# 5V_Regulator.net
KiCad netlist of a schematic drawn in Altium Designer
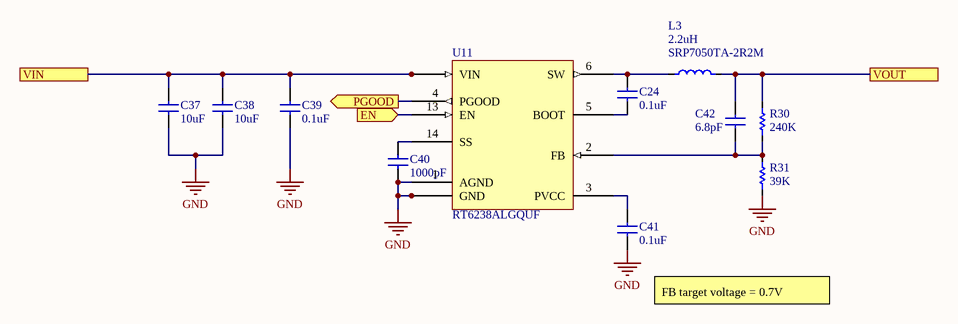
[diagram p0: 5V_Regulator.SchDoc]

(export (version "E")
  (design (tool "Eeschema 10.0.6"))
  (components
    (comp (ref "C24")
      (value "0.1uF")
      (footprint "0603_CAPACITOR")
      (description "CAP CERM 0.1uF 10% 50V 0603")
      (fields
        (field (name "VOLTAGE") "50V")
        (field (name "Comment") "CAP 0.1uF 50V X7R")
        (field (name "SVP CREATOR") "Spencer Berglund")
      )
      (libsource (lib "capacitor") (part "C_0603_0.1uF_50V_10%"))
    )
    (comp (ref "C37")
      (value "10uF")
      (footprint "1206_CAPACITOR")
      (description "CAP CERM 10uF 20% 50V 1206")
      (fields
        (field (name "VOLTAGE") "50V")
        (field (name "Comment") "CAP 10uF 50V X5R")
        (field (name "SVP CREATOR") "Spencer Berglund")
      )
      (libsource (lib "capacitor") (part "C_1206_10uF_50V_20%"))
    )
    (comp (ref "C38")
      (value "10uF")
      (footprint "1206_CAPACITOR")
      (description "CAP CERM 10uF 20% 50V 1206")
      (fields
        (field (name "VOLTAGE") "50V")
        (field (name "Comment") "CAP 10uF 50V X5R")
        (field (name "SVP CREATOR") "Spencer Berglund")
      )
      (libsource (lib "capacitor") (part "C_1206_10uF_50V_20%"))
    )
    (comp (ref "C39")
      (value "0.1uF")
      (footprint "0603_CAPACITOR")
      (description "CAP CERM 0.1uF 10% 50V 0603")
      (fields
        (field (name "VOLTAGE") "50V")
        (field (name "Comment") "CAP 0.1uF 50V X7R")
        (field (name "SVP CREATOR") "Spencer Berglund")
      )
      (libsource (lib "capacitor") (part "C_0603_0.1uF_50V_10%"))
    )
    (comp (ref "C40")
      (value "1000pF")
      (footprint "0603_CAPACITOR")
      (description "CAP CERM 1000pF 10% 50V 0603")
      (fields
        (field (name "VOLTAGE") "50V")
        (field (name "Comment") "CAP 1000pF 50V X7R")
        (field (name "SVP CREATOR") "Spencer Berglund")
      )
      (libsource (lib "capacitor") (part "C_0603_1000pF_50V_10%"))
    )
    (comp (ref "C41")
      (value "0.1uF")
      (footprint "0603_CAPACITOR")
      (description "CAP CERM 0.1uF 10% 50V 0603")
      (fields
        (field (name "VOLTAGE") "50V")
        (field (name "Comment") "CAP 0.1uF 50V X7R")
        (field (name "SVP CREATOR") "Spencer Berglund")
      )
      (libsource (lib "capacitor") (part "C_0603_0.1uF_50V_10%"))
    )
    (comp (ref "C42")
      (value "6.8pF")
      (footprint "0603_CAPACITOR")
      (description "CAP CERM 6.8pF 10% 50V 0603")
      (fields
        (field (name "VOLTAGE") "50V")
        (field (name "Comment") "CAP 6.8pF 50V NP0")
        (field (name "SVP CREATOR") "Spencer Berglund")
      )
      (libsource (lib "capacitor") (part "C_0603_6.8pF_50V_10%"))
    )
    (comp (ref "L3")
      (value "SRP7050TA-2R2M")
      (footprint "L_SRP7050TA")
      (description "2.2µH Shielded Wirewound Inductor 10A 12 mOhm Max Nonstandard")
      (fields
        (field (name "MANUFACTURER") "Bourns")
        (field (name "TOLERANCE") "20%")
        (field (name "ALTIUM_VALUE") "2.2uH")
      )
      (libsource (lib "inductor") (part "L_SRP7050TA-2R2M"))
    )
    (comp (ref "R30")
      (value "240K")
      (footprint "0603_Resistor")
      (description "Generic 0603 Resistor")
      (fields (field (name "TOLERANCE") "±1%") (field (name "MANUFACTURER") "Yageo"))
      (libsource (lib "resistor") (part "R_0603_generic_1%"))
    )
    (comp (ref "R31")
      (value "39K")
      (footprint "0603_Resistor")
      (description "Generic 0603 Resistor")
      (fields (field (name "TOLERANCE") "±1%") (field (name "MANUFACTURER") "Yageo"))
      (libsource (lib "resistor") (part "R_0603_generic_1%"))
    )
    (comp (ref "U11")
      (value "RT6238ALGQUF")
      (footprint "UFQFN-14")
      (description "Buck Switching Regulator IC Positive Adjustable 0.7V 1 Output 8A 14-UFQFN")
      (libsource (lib "ic") (part "U_RT6238A"))
    )
  )
  (nets
    (net (code "1") (name "/EN") (class "Default")
      (node (ref "U11") (pin "13") (pinfunction "EN_13") (pintype "input"))
    )
    (net (code "2") (name "/PGOOD") (class "Default")
      (node (ref "U11") (pin "4") (pinfunction "PGOOD_4") (pintype "output"))
    )
    (net (code "3") (name "/VIN") (class "Default")
      (node (ref "C37") (pin "1") (pinfunction "1_1") (pintype "passive"))
      (node (ref "C38") (pin "1") (pinfunction "1_1") (pintype "passive"))
      (node (ref "C39") (pin "1") (pinfunction "1_1") (pintype "passive"))
      (node (ref "U11") (pin "7") (pinfunction "VIN_7") (pintype "input"))
      (node (ref "U11") (pin "8") (pinfunction "VIN_8") (pintype "input"))
    )
    (net (code "4") (name "/VOUT") (class "Default")
      (node (ref "C42") (pin "1") (pinfunction "1_1") (pintype "passive"))
      (node (ref "L3") (pin "2") (pinfunction "2_2") (pintype "passive"))
      (node (ref "R30") (pin "2") (pinfunction "2_2") (pintype "passive"))
    )
    (net (code "5") (name "GND") (class "Default")
      (node (ref "C37") (pin "2") (pinfunction "2_2") (pintype "passive"))
      (node (ref "C38") (pin "2") (pinfunction "2_2") (pintype "passive"))
      (node (ref "C39") (pin "2") (pinfunction "2_2") (pintype "passive"))
      (node (ref "C40") (pin "2") (pinfunction "2_2") (pintype "passive"))
      (node (ref "C41") (pin "2") (pinfunction "2_2") (pintype "passive"))
      (node (ref "R31") (pin "1") (pinfunction "1_1") (pintype "passive"))
      (node (ref "U11") (pin "1") (pinfunction "AGND_1") (pintype "power_in"))
      (node (ref "U11") (pin "10") (pinfunction "GND_10") (pintype "power_in"))
      (node (ref "U11") (pin "11") (pinfunction "GND_11") (pintype "power_in"))
      (node (ref "U11") (pin "12") (pinfunction "GND_12") (pintype "power_in"))
      (node (ref "U11") (pin "9") (pinfunction "GND_9") (pintype "power_in"))
    )
    (net (code "6") (name "Net-(U11-BOOT)") (class "Default")
      (node (ref "C24") (pin "2") (pinfunction "2_2") (pintype "passive"))
      (node (ref "U11") (pin "5") (pinfunction "BOOT_5") (pintype "passive"))
    )
    (net (code "7") (name "Net-(U11-FB)") (class "Default")
      (node (ref "C42") (pin "2") (pinfunction "2_2") (pintype "passive"))
      (node (ref "R30") (pin "1") (pinfunction "1_1") (pintype "passive"))
      (node (ref "R31") (pin "2") (pinfunction "2_2") (pintype "passive"))
      (node (ref "U11") (pin "2") (pinfunction "FB_2") (pintype "input"))
    )
    (net (code "8") (name "Net-(U11-PVCC)") (class "Default")
      (node (ref "C41") (pin "1") (pinfunction "1_1") (pintype "passive"))
      (node (ref "U11") (pin "3") (pinfunction "PVCC_3") (pintype "power_in"))
    )
    (net (code "9") (name "Net-(U11-SS)") (class "Default")
      (node (ref "C40") (pin "1") (pinfunction "1_1") (pintype "passive"))
      (node (ref "U11") (pin "14") (pinfunction "SS_14") (pintype "passive"))
    )
    (net (code "10") (name "Net-(U11-SW)") (class "Default")
      (node (ref "C24") (pin "1") (pinfunction "1_1") (pintype "passive"))
      (node (ref "L3") (pin "1") (pinfunction "1_1") (pintype "passive"))
      (node (ref "U11") (pin "6") (pinfunction "SW_6") (pintype "output"))
    )
  )
)
